# Sheet1.net
KiCad netlist of a schematic drawn in Altium Designer
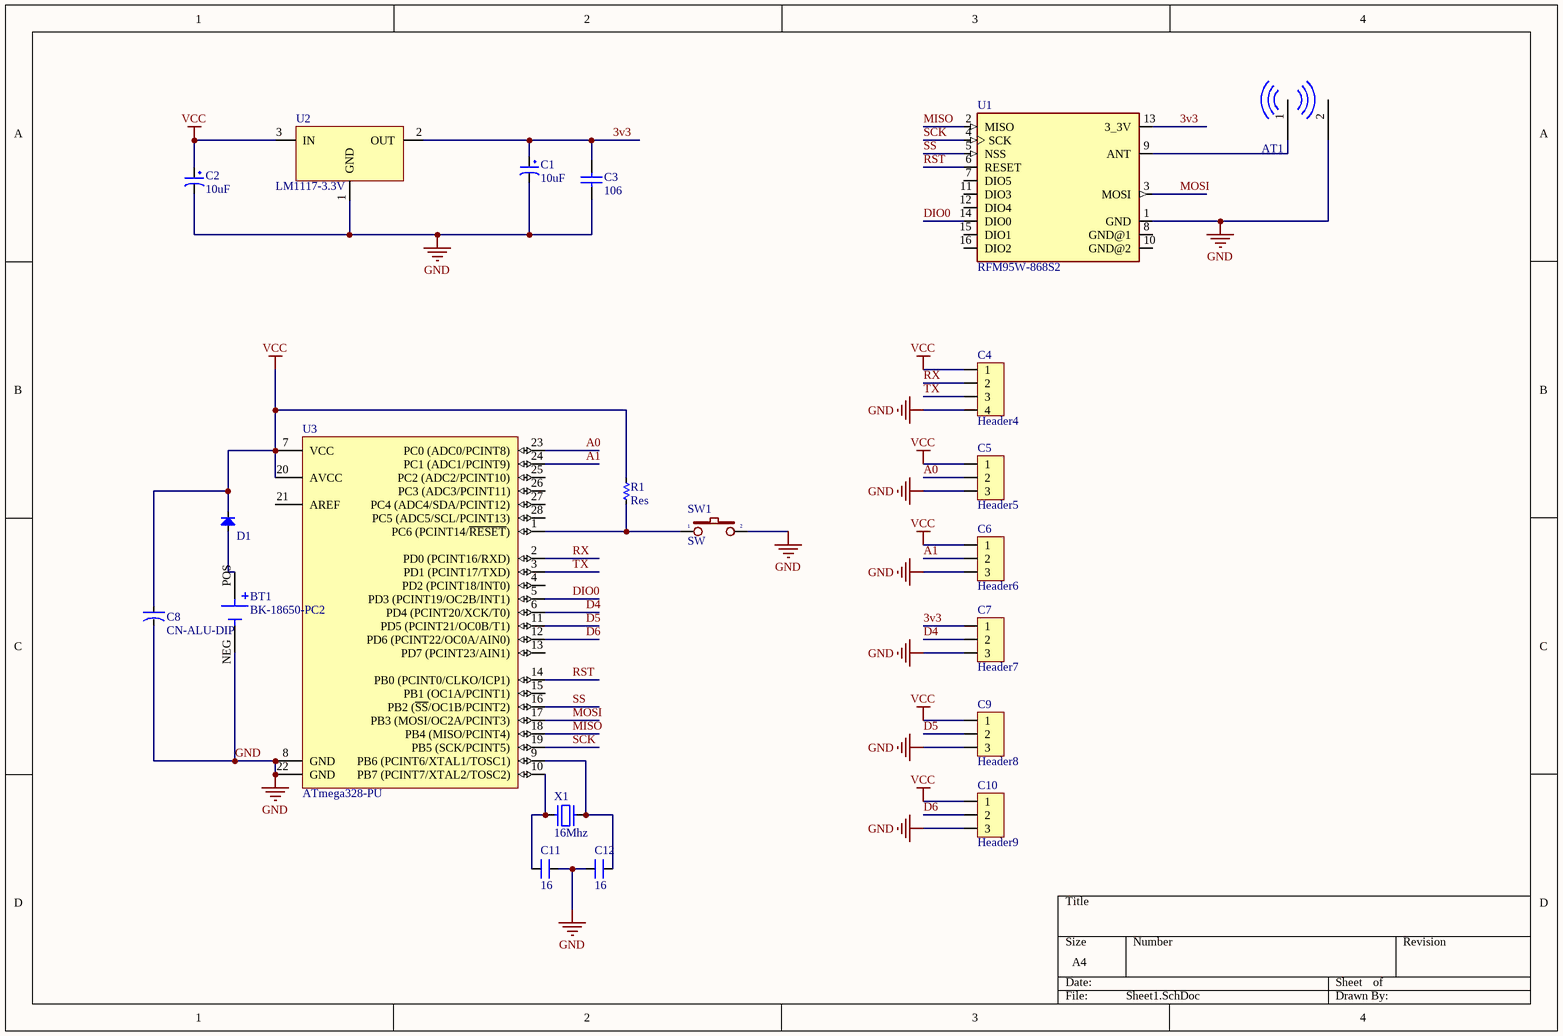
[diagram p0: Sheet1.SchDoc]

(export (version "E")
  (design (tool "Eeschema 10.0.6"))
  (components
    (comp (ref "AT1")
      (value "IPEX_CON")
      (footprint "U.FL/UMCC")
      (description "IPEX CONNECTER ANTENNA GPS GSM")
      (fields (field (name "MPN") "LTI-IPXSM66AL"))
      (libsource (lib "BYTECH_HW_LIB_2019 (1)") (part "LTI-IPXSM66AL"))
    )
    (comp (ref "BT1")
      (value "BK-18650-PC2")
      (footprint "BAT_BK-18650-PC2")
      (description "Battery Holder _Open_ 18650 1 Cell PC Pin")
      (fields (field (name "MF") "MPD"))
      (libsource (lib "BK-18650-PC2") (part "BK-18650-PC2"))
    )
    (comp (ref "C1")
      (value "10uF")
      (footprint "tu hoa 4mm")
      (description "Cắm")
      (libsource (lib "Altium_Lib_by_KhueNguyenCreator") (part "Tu Hoa 10uF 25V 4x7"))
    )
    (comp (ref "C2")
      (value "10uF")
      (footprint "tu hoa 4mm")
      (description "Cắm")
      (libsource (lib "Altium_Lib_by_KhueNguyenCreator") (part "Tu Hoa 10uF 25V 4x7"))
    )
    (comp (ref "C3")
      (value "106")
      (footprint "Tu 0805")
      (description "Dán")
      (libsource (lib "THU VIEN SCH") (part "Tu 0805 106 16V 10%"))
    )
    (comp (ref "C4")
      (value "Header4")
      (footprint "HDR4")
      (description "Header IDC, 4 x 1 Pin Vertical 2.54mm Pitch (Non-Boxed, Male)")
      (fields
        (field (name "MANUFACTURER") "Würth Elektronik eiSos GmbH")
        (field (name "PARTNO") "613002143121")
        (field (name "CREATED BY") "Karrer Zheng")
      )
      (libsource (lib "LIBRARY") (part "Header4"))
    )
    (comp (ref "C5")
      (value "Header5")
      (footprint "HDR3")
      (description "Header IDC, 3 x 1 Pin Vertical 2.54mm Pitch (Non-Boxed, Male)")
      (fields
        (field (name "MANUFACTURER") "Würth Elektronik eiSos GmbH")
        (field (name "PARTNO") "613002143121")
        (field (name "CREATED BY") "Karrer Zheng")
      )
      (libsource (lib "LIBRARY") (part "Header3"))
    )
    (comp (ref "C6")
      (value "Header6")
      (footprint "HDR3")
      (description "Header IDC, 3 x 1 Pin Vertical 2.54mm Pitch (Non-Boxed, Male)")
      (fields
        (field (name "MANUFACTURER") "Würth Elektronik eiSos GmbH")
        (field (name "PARTNO") "613002143121")
        (field (name "CREATED BY") "Karrer Zheng")
      )
      (libsource (lib "LIBRARY") (part "Header3"))
    )
    (comp (ref "C7")
      (value "Header7")
      (footprint "HDR3")
      (description "Header IDC, 3 x 1 Pin Vertical 2.54mm Pitch (Non-Boxed, Male)")
      (fields
        (field (name "MANUFACTURER") "Würth Elektronik eiSos GmbH")
        (field (name "PARTNO") "613002143121")
        (field (name "CREATED BY") "Karrer Zheng")
      )
      (libsource (lib "LIBRARY") (part "Header3"))
    )
    (comp (ref "C8")
      (value "CN-ALU-DIP")
      (footprint "CA-ALU-10BL")
      (description "Capacitor (Semiconductor SIM Model)")
      (fields (field (name "PUBLISHER") "Altium Limited"))
      (libsource (lib "LIBRARY") (part "CN-ALU-DIP"))
    )
    (comp (ref "C9")
      (value "Header8")
      (footprint "HDR3")
      (description "Header IDC, 3 x 1 Pin Vertical 2.54mm Pitch (Non-Boxed, Male)")
      (fields
        (field (name "MANUFACTURER") "Würth Elektronik eiSos GmbH")
        (field (name "PARTNO") "613002143121")
        (field (name "CREATED BY") "Karrer Zheng")
      )
      (libsource (lib "LIBRARY") (part "Header3"))
    )
    (comp (ref "C10")
      (value "Header9")
      (footprint "HDR3")
      (description "Header IDC, 3 x 1 Pin Vertical 2.54mm Pitch (Non-Boxed, Male)")
      (fields
        (field (name "MANUFACTURER") "Würth Elektronik eiSos GmbH")
        (field (name "PARTNO") "613002143121")
        (field (name "CREATED BY") "Karrer Zheng")
      )
      (libsource (lib "LIBRARY") (part "Header3"))
    )
    (comp (ref "C11")
      (value "16")
      (footprint "CN1.5")
      (description "Cap np 682pF => 104pF")
      (libsource (lib "syhaunguyen") (part "CN1.5"))
    )
    (comp (ref "C12")
      (value "16")
      (footprint "CN1.5")
      (description "Cap np 682pF => 104pF")
      (libsource (lib "syhaunguyen") (part "CN1.5"))
    )
    (comp (ref "D1")
      (value "Diode")
      (footprint "DIO-1A")
      (description "Default Diode")
      (fields (field (name "PUBLISHER") "Altium Limited"))
      (libsource (lib "LIBRARY") (part "Diode"))
    )
    (comp (ref "R1")
      (value "Res")
      (footprint "RES-1/8W")
      (fields
        (field (name "MANUFACTURER") "Generic Components")
        (field (name "PUBLISHER") "Altium Hobart Technology Centre")
      )
      (libsource (lib "LIBRARY") (part "Res"))
    )
    (comp (ref "SW1")
      (value "SW")
      (footprint "SW1-SMD")
      (description "Switch button 2 pin")
      (libsource (lib "LIBRARY") (part "SW2"))
    )
    (comp (ref "U1")
      (value "RFM95W-868S2")
      (footprint "XCVR_RFM95W-868S2")
      (description "General ISM < 1GHz LoRaâ„¢ Transceiver Module 868MHz Antenna Not Included Surface Mount")
      (fields (field (name "MF") "RF"))
      (libsource (lib "RFM95W-868S2") (part "RFM95W-868S2"))
    )
    (comp (ref "U2")
      (value "LM1117-3.3V")
      (footprint "SOT223")
      (description "800mA Low-Dropout Linear Regulator")
      (fields (field (name "CREATOR") "Nguyen Ba Bien"))
      (libsource (lib "LIBRARY") (part "LM1117"))
    )
    (comp (ref "U3")
      (value "ATmega328-PU")
      (footprint "DIP28")
      (fields (field (name "PUBLISHER") "Altium Limited"))
      (libsource (lib "LIBRARY") (part "ATmega328-PU"))
    )
    (comp (ref "X1")
      (value "16Mhz")
      (footprint "XTAL-RU49/4")
      (description "Crystal, 32.768 KHz, -40 to 85 degC, 3.2 x 1.5 x 0.9 mm SMD")
      (libsource (lib "LIBRARY") (part "XT2"))
    )
  )
  (nets
    (net (code "1") (name "/3v3") (class "Default")
      (node (ref "C1") (pin "1") (pinfunction "1_1") (pintype "passive"))
      (node (ref "C3") (pin "1") (pinfunction "1_1") (pintype "passive"))
      (node (ref "C7") (pin "1") (pinfunction "1_1") (pintype "passive"))
      (node (ref "U1") (pin "13") (pinfunction "3_3V_13") (pintype "power_in"))
      (node (ref "U2") (pin "2") (pinfunction "OUT_2") (pintype "passive"))
    )
    (net (code "2") (name "/A0") (class "Default")
      (node (ref "C5") (pin "2") (pinfunction "2_2") (pintype "passive"))
      (node (ref "U3") (pin "23") (pinfunction "PC0_(ADC0/PCINT8)_23") (pintype "bidirectional"))
    )
    (net (code "3") (name "/A1") (class "Default")
      (node (ref "C6") (pin "2") (pinfunction "2_2") (pintype "passive"))
      (node (ref "U3") (pin "24") (pinfunction "PC1_(ADC1/PCINT9)_24") (pintype "bidirectional"))
    )
    (net (code "4") (name "/D4") (class "Default")
      (node (ref "C7") (pin "2") (pinfunction "2_2") (pintype "passive"))
      (node (ref "U3") (pin "6") (pinfunction "PD4_(PCINT20/XCK/T0)_6") (pintype "bidirectional"))
    )
    (net (code "5") (name "/D5") (class "Default")
      (node (ref "C9") (pin "2") (pinfunction "2_2") (pintype "passive"))
      (node (ref "U3") (pin "11") (pinfunction "PD5_(PCINT21/OC0B/T1)_11") (pintype "bidirectional"))
    )
    (net (code "6") (name "/D6") (class "Default")
      (node (ref "C10") (pin "2") (pinfunction "2_2") (pintype "passive"))
      (node (ref "U3") (pin "12") (pinfunction "PD6_(PCINT22/OC0A/AIN0)_12") (pintype "bidirectional"))
    )
    (net (code "7") (name "/DIO0") (class "Default")
      (node (ref "U1") (pin "14") (pinfunction "DIO0_14") (pintype "bidirectional"))
      (node (ref "U3") (pin "5") (pinfunction "PD3_(PCINT19/OC2B/INT1)_5") (pintype "bidirectional"))
    )
    (net (code "8") (name "/MISO") (class "Default")
      (node (ref "U1") (pin "2") (pinfunction "MISO_2") (pintype "input"))
      (node (ref "U3") (pin "18") (pinfunction "PB4_(MISO/PCINT4)_18") (pintype "bidirectional"))
    )
    (net (code "9") (name "/MOSI") (class "Default")
      (node (ref "U1") (pin "3") (pinfunction "MOSI_3") (pintype "output"))
      (node (ref "U3") (pin "17") (pinfunction "PB3_(MOSI/OC2A/PCINT3)_17") (pintype "bidirectional"))
    )
    (net (code "10") (name "/RST") (class "Default")
      (node (ref "U1") (pin "6") (pinfunction "RESET_6") (pintype "bidirectional"))
      (node (ref "U3") (pin "14") (pinfunction "PB0_(PCINT0/CLKO/ICP1)_14") (pintype "bidirectional"))
    )
    (net (code "11") (name "/RX") (class "Default")
      (node (ref "C4") (pin "2") (pinfunction "2_2") (pintype "passive"))
      (node (ref "U3") (pin "2") (pinfunction "PD0_(PCINT16/RXD)_2") (pintype "bidirectional"))
    )
    (net (code "12") (name "/SCK") (class "Default")
      (node (ref "U1") (pin "4") (pinfunction "SCK_4") (pintype "input"))
      (node (ref "U3") (pin "19") (pinfunction "PB5_(SCK/PCINT5)_19") (pintype "bidirectional"))
    )
    (net (code "13") (name "/SS") (class "Default")
      (node (ref "U1") (pin "5") (pinfunction "NSS_5") (pintype "input"))
      (node (ref "U3") (pin "16") (pinfunction "PB2_(~{SS}/OC1B/PCINT2)_16") (pintype "bidirectional"))
    )
    (net (code "14") (name "/TX") (class "Default")
      (node (ref "C4") (pin "3") (pinfunction "3_3") (pintype "passive"))
      (node (ref "U3") (pin "3") (pinfunction "PD1_(PCINT17/TXD)_3") (pintype "bidirectional"))
    )
    (net (code "15") (name "GND") (class "Default")
      (node (ref "AT1") (pin "2") (pinfunction "0_2") (pintype "passive"))
      (node (ref "BT1") (pin "NEG") (pinfunction "NEG_NEG") (pintype "passive"))
      (node (ref "C1") (pin "2") (pinfunction "2_2") (pintype "passive"))
      (node (ref "C10") (pin "3") (pinfunction "3_3") (pintype "passive"))
      (node (ref "C11") (pin "2") (pinfunction "2_2") (pintype "passive"))
      (node (ref "C12") (pin "1") (pinfunction "1_1") (pintype "passive"))
      (node (ref "C2") (pin "2") (pinfunction "2_2") (pintype "passive"))
      (node (ref "C3") (pin "2") (pinfunction "2_2") (pintype "passive"))
      (node (ref "C4") (pin "4") (pinfunction "4_4") (pintype "passive"))
      (node (ref "C5") (pin "3") (pinfunction "3_3") (pintype "passive"))
      (node (ref "C6") (pin "3") (pinfunction "3_3") (pintype "passive"))
      (node (ref "C7") (pin "3") (pinfunction "3_3") (pintype "passive"))
      (node (ref "C8") (pin "2") (pinfunction "2_2") (pintype "passive"))
      (node (ref "C9") (pin "3") (pinfunction "3_3") (pintype "passive"))
      (node (ref "SW1") (pin "2") (pinfunction "2_2") (pintype "passive"))
      (node (ref "U1") (pin "1") (pinfunction "GND_1") (pintype "power_in"))
      (node (ref "U2") (pin "1") (pinfunction "GND_1") (pintype "passive"))
      (node (ref "U3") (pin "22") (pinfunction "GND_22") (pintype "power_in"))
      (node (ref "U3") (pin "8") (pinfunction "GND_8") (pintype "power_in"))
    )
    (net (code "16") (name "Net-(AT1-AT)") (class "Default")
      (node (ref "AT1") (pin "1") (pinfunction "AT_1") (pintype "passive"))
      (node (ref "U1") (pin "9") (pinfunction "ANT_9") (pintype "passive"))
    )
    (net (code "17") (name "Net-(D1-A)") (class "Default")
      (node (ref "BT1") (pin "POS") (pinfunction "POS_POS") (pintype "passive"))
      (node (ref "D1") (pin "1") (pinfunction "A_1") (pintype "passive"))
    )
    (net (code "18") (name "Net-(U3-PB6_(PCINT6{slash}XTAL1{slash}TOSC1))") (class "Default")
      (node (ref "C12") (pin "2") (pinfunction "2_2") (pintype "passive"))
      (node (ref "U3") (pin "9") (pinfunction "PB6_(PCINT6/XTAL1/TOSC1)_9") (pintype "bidirectional"))
      (node (ref "X1") (pin "2") (pinfunction "2_2") (pintype "passive"))
    )
    (net (code "19") (name "Net-(U3-PB7_(PCINT7{slash}XTAL2{slash}TOSC2))") (class "Default")
      (node (ref "C11") (pin "1") (pinfunction "1_1") (pintype "passive"))
      (node (ref "U3") (pin "10") (pinfunction "PB7_(PCINT7/XTAL2/TOSC2)_10") (pintype "bidirectional"))
      (node (ref "X1") (pin "1") (pinfunction "1_1") (pintype "passive"))
    )
    (net (code "20") (name "Net-(U3-PC6_(PCINT14{slash}~{RESET}))") (class "Default")
      (node (ref "R1") (pin "2") (pinfunction "2_2") (pintype "passive"))
      (node (ref "SW1") (pin "1") (pinfunction "1_1") (pintype "passive"))
      (node (ref "U3") (pin "1") (pinfunction "PC6_(PCINT14/~{RESET})_1") (pintype "bidirectional"))
    )
    (net (code "21") (name "VCC") (class "Default")
      (node (ref "C10") (pin "1") (pinfunction "1_1") (pintype "passive"))
      (node (ref "C2") (pin "1") (pinfunction "1_1") (pintype "passive"))
      (node (ref "C4") (pin "1") (pinfunction "1_1") (pintype "passive"))
      (node (ref "C5") (pin "1") (pinfunction "1_1") (pintype "passive"))
      (node (ref "C6") (pin "1") (pinfunction "1_1") (pintype "passive"))
      (node (ref "C8") (pin "1") (pinfunction "1_1") (pintype "passive"))
      (node (ref "C9") (pin "1") (pinfunction "1_1") (pintype "passive"))
      (node (ref "D1") (pin "2") (pinfunction "K_2") (pintype "passive"))
      (node (ref "R1") (pin "1") (pinfunction "1_1") (pintype "passive"))
      (node (ref "U2") (pin "3") (pinfunction "IN_3") (pintype "passive"))
      (node (ref "U3") (pin "20") (pinfunction "AVCC_20") (pintype "power_in"))
      (node (ref "U3") (pin "7") (pinfunction "VCC_7") (pintype "power_in"))
    )
    (net (code "22") (name "unconnected-(U1-DIO1-Pad15)") (class "Default")
      (node (ref "U1") (pin "15") (pinfunction "DIO1_15") (pintype "bidirectional"))
    )
    (net (code "23") (name "unconnected-(U1-DIO2-Pad16)") (class "Default")
      (node (ref "U1") (pin "16") (pinfunction "DIO2_16") (pintype "bidirectional"))
    )
    (net (code "24") (name "unconnected-(U1-DIO3-Pad11)") (class "Default")
      (node (ref "U1") (pin "11") (pinfunction "DIO3_11") (pintype "bidirectional"))
    )
    (net (code "25") (name "unconnected-(U1-DIO4-Pad12)") (class "Default")
      (node (ref "U1") (pin "12") (pinfunction "DIO4_12") (pintype "bidirectional"))
    )
    (net (code "26") (name "unconnected-(U1-DIO5-Pad7)") (class "Default")
      (node (ref "U1") (pin "7") (pinfunction "DIO5_7") (pintype "bidirectional"))
    )
    (net (code "27") (name "unconnected-(U1-GND@1-Pad8)") (class "Default")
      (node (ref "U1") (pin "8") (pinfunction "GND@1_8") (pintype "power_in"))
    )
    (net (code "28") (name "unconnected-(U1-GND@2-Pad10)") (class "Default")
      (node (ref "U1") (pin "10") (pinfunction "GND@2_10") (pintype "power_in"))
    )
    (net (code "29") (name "unconnected-(U3-AREF-Pad21)") (class "Default")
      (node (ref "U3") (pin "21") (pinfunction "AREF_21") (pintype "power_in"))
    )
    (net (code "30") (name "unconnected-(U3-PB1_(OC1A{slash}PCINT1)-Pad15)") (class "Default")
      (node (ref "U3") (pin "15") (pinfunction "PB1_(OC1A/PCINT1)_15") (pintype "bidirectional"))
    )
    (net (code "31") (name "unconnected-(U3-PC2_(ADC2{slash}PCINT10)-Pad25)") (class "Default")
      (node (ref "U3") (pin "25") (pinfunction "PC2_(ADC2/PCINT10)_25") (pintype "bidirectional"))
    )
    (net (code "32") (name "unconnected-(U3-PC3_(ADC3{slash}PCINT11)-Pad26)") (class "Default")
      (node (ref "U3") (pin "26") (pinfunction "PC3_(ADC3/PCINT11)_26") (pintype "bidirectional"))
    )
    (net (code "33") (name "unconnected-(U3-PC4_(ADC4{slash}SDA{slash}PCINT12)-Pad27)") (class "Default")
      (node (ref "U3") (pin "27") (pinfunction "PC4_(ADC4/SDA/PCINT12)_27") (pintype "bidirectional"))
    )
    (net (code "34") (name "unconnected-(U3-PC5_(ADC5{slash}SCL{slash}PCINT13)-Pad28)") (class "Default")
      (node (ref "U3") (pin "28") (pinfunction "PC5_(ADC5/SCL/PCINT13)_28") (pintype "bidirectional"))
    )
    (net (code "35") (name "unconnected-(U3-PD2_(PCINT18{slash}INT0)-Pad4)") (class "Default")
      (node (ref "U3") (pin "4") (pinfunction "PD2_(PCINT18/INT0)_4") (pintype "bidirectional"))
    )
    (net (code "36") (name "unconnected-(U3-PD7_(PCINT23{slash}AIN1)-Pad13)") (class "Default")
      (node (ref "U3") (pin "13") (pinfunction "PD7_(PCINT23/AIN1)_13") (pintype "bidirectional"))
    )
  )
)
